# PIXRACER-POWER-R12.net
KiCad netlist of a schematic drawn in Altium Designer
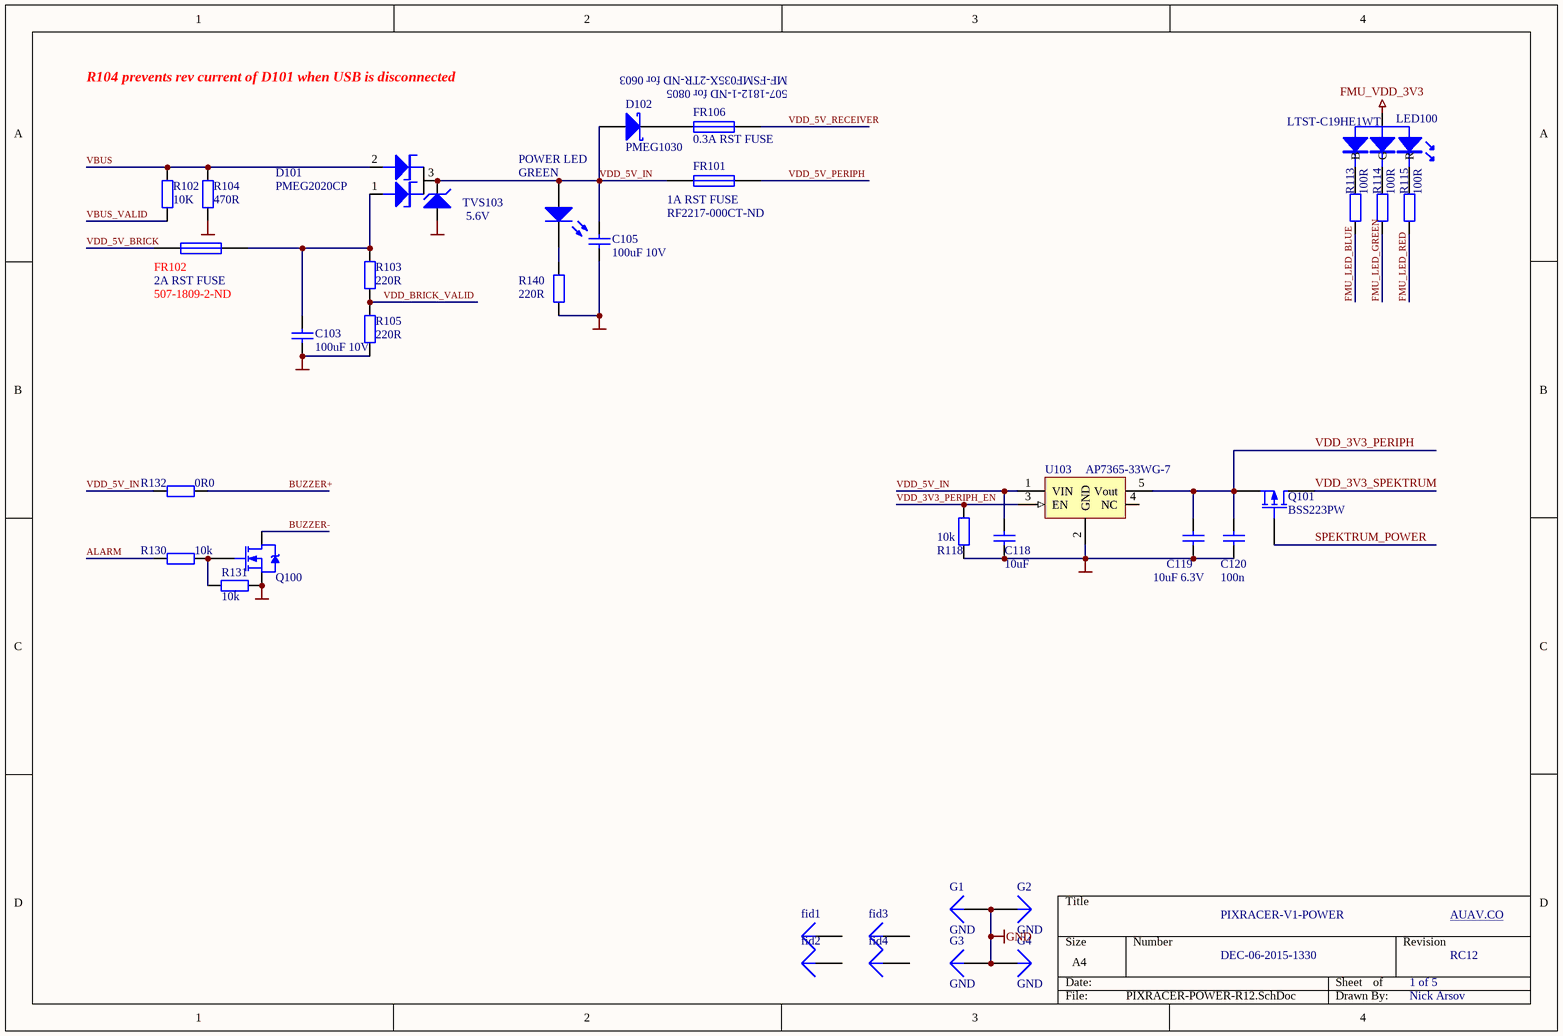
[diagram p0: PIXRACER-POWER-R12.SchDoc]

(export (version "E")
  (design (tool "Eeschema 10.0.6"))
  (components
    (comp (ref "C103")
      (value "100uF 10V")
      (footprint "0805A")
      (description "Capacitor")
      (fields (field (name "PUBLISHER") "Altium Limited"))
      (libsource (lib "Miscellaneous Devices") (part "Cap"))
    )
    (comp (ref "C105")
      (value "100uF 10V")
      (footprint "0805A")
      (description "Capacitor")
      (fields (field (name "PUBLISHER") "Altium Limited"))
      (libsource (lib "Miscellaneous Devices") (part "Cap"))
    )
    (comp (ref "C118")
      (value "10uF")
      (footprint "0603A")
      (description "Capacitor")
      (fields (field (name "PUBLISHER") "Altium Limited"))
      (libsource (lib "Miscellaneous Devices") (part "Cap"))
    )
    (comp (ref "C119")
      (value "10uF 6.3V")
      (footprint "0603A")
      (description "Capacitor")
      (fields (field (name "PUBLISHER") "Altium Limited"))
      (libsource (lib "Miscellaneous Devices") (part "Cap"))
    )
    (comp (ref "C120")
      (value "100n")
      (footprint "0603A")
      (description "Capacitor")
      (fields (field (name "PUBLISHER") "Altium Limited"))
      (libsource (lib "Miscellaneous Devices") (part "Cap"))
    )
    (comp (ref "D101")
      (value "PMEG2020CP")
      (footprint "pmeg2020cp")
      (libsource (lib "My_Altium") (part "PMEG2020CP"))
    )
    (comp (ref "D102")
      (value "PMEG1030")
      (footprint "sod323f")
      (description "Schottky Diode")
      (fields (field (name "PUBLISHER") "Altium Limited"))
      (libsource (lib "Miscellaneous Devices") (part "D Schottky"))
    )
    (comp (ref "fid1")
      (value "~")
      (footprint "SMT_PAD")
      (description "Plug")
      (fields (field (name "PUBLISHER") "Altium Limited"))
      (libsource (lib "Miscellaneous Connectors") (part "Plug"))
    )
    (comp (ref "fid2")
      (value "~")
      (footprint "SMT_PAD")
      (description "Plug")
      (fields (field (name "PUBLISHER") "Altium Limited"))
      (libsource (lib "Miscellaneous Connectors") (part "Plug"))
    )
    (comp (ref "fid3")
      (value "~")
      (footprint "SMT_PAD")
      (description "Plug")
      (fields (field (name "PUBLISHER") "Altium Limited"))
      (libsource (lib "Miscellaneous Connectors") (part "Plug"))
    )
    (comp (ref "fid4")
      (value "~")
      (footprint "SMT_PAD")
      (description "Plug")
      (fields (field (name "PUBLISHER") "Altium Limited"))
      (libsource (lib "Miscellaneous Connectors") (part "Plug"))
    )
    (comp (ref "FR101")
      (value "1A RST FUSE")
      (footprint "0805A")
      (description "Fuse")
      (fields (field (name "DIGIKEY") "RF2217-000CT-ND") (field (name "PUBLISHER") "Altium Limited"))
      (libsource (lib "Miscellaneous Devices") (part "Fuse 1"))
    )
    (comp (ref "FR102")
      (value "2A RST FUSE")
      (footprint "1206A")
      (description "Fuse")
      (fields (field (name "DIGIKEY") "507-1809-2-ND") (field (name "PUBLISHER") "Altium Limited"))
      (libsource (lib "Miscellaneous Devices") (part "Fuse 1"))
    )
    (comp (ref "FR106")
      (value "0.3A RST FUSE")
      (footprint "0805A")
      (description "Fuse")
      (fields (field (name "PUBLISHER") "Altium Limited"))
      (libsource (lib "Miscellaneous Devices") (part "Fuse 1"))
    )
    (comp (ref "G1")
      (value "GND")
      (description "Plug")
      (fields (field (name "PUBLISHER") "Altium Limited"))
      (libsource (lib "Miscellaneous Connectors") (part "Plug"))
    )
    (comp (ref "G2")
      (value "GND")
      (description "Plug")
      (fields (field (name "PUBLISHER") "Altium Limited"))
      (libsource (lib "Miscellaneous Connectors") (part "Plug"))
    )
    (comp (ref "G3")
      (value "GND")
      (description "Plug")
      (fields (field (name "PUBLISHER") "Altium Limited"))
      (libsource (lib "Miscellaneous Connectors") (part "Plug"))
    )
    (comp (ref "G4")
      (value "GND")
      (description "Plug")
      (fields (field (name "PUBLISHER") "Altium Limited"))
      (libsource (lib "Miscellaneous Connectors") (part "Plug"))
    )
    (comp (ref "LED100")
      (value "LTST-C19HE1WT")
      (footprint "LTST-C19HE1WT")
      (libsource (lib "My_Altium") (part "RGB_LED_5MM"))
    )
    (comp (ref "POWER LED")
      (value "GREEN")
      (footprint "0603A")
      (description "Typical INFRARED GaAs LED")
      (fields (field (name "PUBLISHER") "Altium Limited"))
      (libsource (lib "Miscellaneous Devices") (part "LED0"))
    )
    (comp (ref "Q100")
      (value "DMG1012UW")
      (footprint "2N7002-SOT323")
      (description "N-Channel Power MOSFET")
      (fields (field (name "PUBLISHER") "Altium Limited"))
      (libsource (lib "Miscellaneous Devices") (part "NMOS-2"))
    )
    (comp (ref "Q101")
      (value "BSS223PW")
      (footprint "2N7002-SOT323")
      (description "P-Channel MOSFET")
      (fields (field (name "PUBLISHER") "Altium Limited"))
      (libsource (lib "Miscellaneous Devices") (part "MOSFET-P"))
    )
    (comp (ref "R102")
      (value "10K")
      (footprint "0603A")
      (description "Resistor")
      (fields (field (name "PUBLISHER") "Altium Limited"))
      (libsource (lib "") (part "Res2_1"))
    )
    (comp (ref "R103")
      (value "220R")
      (footprint "0603A")
      (description "Resistor")
      (fields (field (name "PUBLISHER") "Altium Limited"))
      (libsource (lib "Miscellaneous Devices") (part "Res2"))
    )
    (comp (ref "R104")
      (value "470R")
      (footprint "0603A")
      (description "Resistor")
      (fields (field (name "PUBLISHER") "Altium Limited"))
      (libsource (lib "") (part "Res2_1"))
    )
    (comp (ref "R105")
      (value "220R")
      (footprint "0603A")
      (description "Resistor")
      (fields (field (name "PUBLISHER") "Altium Limited"))
      (libsource (lib "Miscellaneous Devices") (part "Res2"))
    )
    (comp (ref "R113")
      (value "100R")
      (footprint "0402A")
      (description "Resistor")
      (fields (field (name "PUBLISHER") "Altium Limited"))
      (libsource (lib "") (part "Res2_1"))
    )
    (comp (ref "R114")
      (value "100R")
      (footprint "0402A")
      (description "Resistor")
      (fields (field (name "PUBLISHER") "Altium Limited"))
      (libsource (lib "") (part "Res2_1"))
    )
    (comp (ref "R115")
      (value "100R")
      (footprint "0402A")
      (description "Resistor")
      (fields (field (name "PUBLISHER") "Altium Limited"))
      (libsource (lib "") (part "Res2_1"))
    )
    (comp (ref "R118")
      (value "10k")
      (footprint "0603A")
      (description "Resistor")
      (fields (field (name "PUBLISHER") "Altium Limited"))
      (libsource (lib "") (part "Res2_1"))
    )
    (comp (ref "R130")
      (value "10k")
      (footprint "0402A")
      (description "Resistor")
      (fields (field (name "PUBLISHER") "Altium Limited"))
      (libsource (lib "") (part "Res2_3"))
    )
    (comp (ref "R131")
      (value "10k")
      (footprint "0402A")
      (description "Resistor")
      (fields (field (name "PUBLISHER") "Altium Limited"))
      (libsource (lib "") (part "Res2_2"))
    )
    (comp (ref "R132")
      (value "0R0")
      (footprint "0402A")
      (description "Resistor")
      (fields (field (name "PUBLISHER") "Altium Limited"))
      (libsource (lib "") (part "Res2_3"))
    )
    (comp (ref "R140")
      (value "220R")
      (footprint "0603A")
      (description "Resistor")
      (fields (field (name "PUBLISHER") "Altium Limited"))
      (libsource (lib "") (part "Res2_1"))
    )
    (comp (ref "TVS103")
      (value "5.6V")
      (footprint "SOD123F")
      (description "Zener Diode")
      (fields (field (name "PUBLISHER") "Altium Limited"))
      (libsource (lib "Miscellaneous Devices") (part "D Zener"))
    )
    (comp (ref "U103")
      (value "AP7365-33WG-7")
      (footprint "SOT23-5")
      (libsource (lib "My_Altium") (part "LP5907-Q1"))
    )
  )
  (nets
    (net (code "1") (name "/ALARM") (class "Default")
      (node (ref "R130") (pin "2") (pinfunction "2_2") (pintype "passive"))
    )
    (net (code "2") (name "/BUZZER+") (class "Default")
      (node (ref "R132") (pin "1") (pinfunction "1_1") (pintype "passive"))
    )
    (net (code "3") (name "/BUZZER-") (class "Default")
      (node (ref "Q100") (pin "1") (pinfunction "D_1") (pintype "passive"))
    )
    (net (code "4") (name "/FMU_LED_BLUE") (class "Default")
      (node (ref "R113") (pin "1") (pinfunction "1_1") (pintype "passive"))
    )
    (net (code "5") (name "/FMU_LED_GREEN") (class "Default")
      (node (ref "R114") (pin "1") (pinfunction "1_1") (pintype "passive"))
    )
    (net (code "6") (name "/FMU_LED_RED") (class "Default")
      (node (ref "R115") (pin "1") (pinfunction "1_1") (pintype "passive"))
    )
    (net (code "7") (name "/SPEKTRUM_POWER") (class "Default")
      (node (ref "Q101") (pin "3") (pinfunction "G_3") (pintype "passive"))
    )
    (net (code "8") (name "/VBUS") (class "Default")
      (node (ref "D101") (pin "2") (pintype "passive"))
      (node (ref "R102") (pin "2") (pinfunction "2_2") (pintype "passive"))
      (node (ref "R104") (pin "2") (pinfunction "2_2") (pintype "passive"))
    )
    (net (code "9") (name "/VBUS_VALID") (class "Default")
      (node (ref "R102") (pin "1") (pinfunction "1_1") (pintype "passive"))
    )
    (net (code "10") (name "/VDD_3V3_PERIPH") (class "Default")
      (node (ref "C119") (pin "2") (pinfunction "2_2") (pintype "passive"))
      (node (ref "C120") (pin "2") (pinfunction "2_2") (pintype "passive"))
      (node (ref "Q101") (pin "2") (pinfunction "S_2") (pintype "passive"))
      (node (ref "U103") (pin "5") (pinfunction "Vout_5") (pintype "power_in"))
    )
    (net (code "11") (name "/VDD_3V3_PERIPH_EN") (class "Default")
      (node (ref "R118") (pin "2") (pinfunction "2_2") (pintype "passive"))
      (node (ref "U103") (pin "3") (pinfunction "EN_3") (pintype "input"))
    )
    (net (code "12") (name "/VDD_3V3_SPEKTRUM") (class "Default")
      (node (ref "Q101") (pin "1") (pinfunction "D_1") (pintype "passive"))
    )
    (net (code "13") (name "/VDD_5V_BRICK") (class "Default")
      (node (ref "FR102") (pin "1") (pinfunction "1_1") (pintype "passive"))
    )
    (net (code "14") (name "/VDD_5V_IN") (class "Default")
      (node (ref "C105") (pin "2") (pinfunction "2_2") (pintype "passive"))
      (node (ref "C118") (pin "2") (pinfunction "2_2") (pintype "passive"))
      (node (ref "D101") (pin "3") (pintype "passive"))
      (node (ref "D102") (pin "1") (pinfunction "A_1") (pintype "passive"))
      (node (ref "FR101") (pin "1") (pinfunction "1_1") (pintype "passive"))
      (node (ref "POWER LED") (pin "1") (pinfunction "A_1") (pintype "passive"))
      (node (ref "R132") (pin "2") (pinfunction "2_2") (pintype "passive"))
      (node (ref "TVS103") (pin "2") (pinfunction "K_2") (pintype "passive"))
      (node (ref "U103") (pin "1") (pinfunction "VIN_1") (pintype "power_in"))
    )
    (net (code "15") (name "/VDD_5V_PERIPH") (class "Default")
      (node (ref "FR101") (pin "2") (pinfunction "2_2") (pintype "passive"))
    )
    (net (code "16") (name "/VDD_5V_RECEIVER") (class "Default")
      (node (ref "FR106") (pin "2") (pinfunction "2_2") (pintype "passive"))
    )
    (net (code "17") (name "/VDD_BRICK_VALID") (class "Default")
      (node (ref "R103") (pin "2") (pinfunction "2_2") (pintype "passive"))
      (node (ref "R105") (pin "1") (pinfunction "1_1") (pintype "passive"))
    )
    (net (code "18") (name "FMU_VDD_3V3") (class "Default")
      (node (ref "LED100") (pin "4") (pinfunction "A_4") (pintype "passive"))
    )
    (net (code "19") (name "GND") (class "Default")
      (node (ref "C103") (pin "1") (pinfunction "1_1") (pintype "passive"))
      (node (ref "C105") (pin "1") (pinfunction "1_1") (pintype "passive"))
      (node (ref "C118") (pin "1") (pinfunction "1_1") (pintype "passive"))
      (node (ref "C119") (pin "1") (pinfunction "1_1") (pintype "passive"))
      (node (ref "C120") (pin "1") (pinfunction "1_1") (pintype "passive"))
      (node (ref "G1") (pin "1") (pinfunction "1_1") (pintype "passive"))
      (node (ref "G2") (pin "1") (pinfunction "1_1") (pintype "passive"))
      (node (ref "G3") (pin "1") (pinfunction "1_1") (pintype "passive"))
      (node (ref "G4") (pin "1") (pinfunction "1_1") (pintype "passive"))
      (node (ref "Q100") (pin "2") (pinfunction "S_2") (pintype "passive"))
      (node (ref "R104") (pin "1") (pinfunction "1_1") (pintype "passive"))
      (node (ref "R105") (pin "2") (pinfunction "2_2") (pintype "passive"))
      (node (ref "R118") (pin "1") (pinfunction "1_1") (pintype "passive"))
      (node (ref "R131") (pin "2") (pinfunction "2_2") (pintype "passive"))
      (node (ref "R140") (pin "1") (pinfunction "1_1") (pintype "passive"))
      (node (ref "TVS103") (pin "1") (pinfunction "A_1") (pintype "passive"))
      (node (ref "U103") (pin "2") (pinfunction "GND_2") (pintype "power_in"))
    )
    (net (code "20") (name "Net-(C103-Pad2)") (class "Default")
      (node (ref "C103") (pin "2") (pinfunction "2_2") (pintype "passive"))
      (node (ref "D101") (pin "1") (pintype "passive"))
      (node (ref "FR102") (pin "2") (pinfunction "2_2") (pintype "passive"))
      (node (ref "R103") (pin "1") (pinfunction "1_1") (pintype "passive"))
    )
    (net (code "21") (name "Net-(D102-K)") (class "Default")
      (node (ref "D102") (pin "2") (pinfunction "K_2") (pintype "passive"))
      (node (ref "FR106") (pin "1") (pinfunction "1_1") (pintype "passive"))
    )
    (net (code "22") (name "Net-(LED100-B)") (class "Default")
      (node (ref "LED100") (pin "3") (pinfunction "B_3") (pintype "passive"))
      (node (ref "R113") (pin "2") (pinfunction "2_2") (pintype "passive"))
    )
    (net (code "23") (name "Net-(LED100-G)") (class "Default")
      (node (ref "LED100") (pin "2") (pinfunction "G_2") (pintype "passive"))
      (node (ref "R114") (pin "2") (pinfunction "2_2") (pintype "passive"))
    )
    (net (code "24") (name "Net-(LED100-R)") (class "Default")
      (node (ref "LED100") (pin "1") (pinfunction "R_1") (pintype "passive"))
      (node (ref "R115") (pin "2") (pinfunction "2_2") (pintype "passive"))
    )
    (net (code "25") (name "Net-(POWER LED-K)") (class "Default")
      (node (ref "POWER LED") (pin "2") (pinfunction "K_2") (pintype "passive"))
      (node (ref "R140") (pin "2") (pinfunction "2_2") (pintype "passive"))
    )
    (net (code "26") (name "Net-(Q100-G)") (class "Default")
      (node (ref "Q100") (pin "3") (pinfunction "G_3") (pintype "passive"))
      (node (ref "R130") (pin "1") (pinfunction "1_1") (pintype "passive"))
      (node (ref "R131") (pin "1") (pinfunction "1_1") (pintype "passive"))
    )
    (net (code "27") (name "unconnected-(U103-NC-Pad4)") (class "Default")
      (node (ref "U103") (pin "4") (pinfunction "NC_4") (pintype "passive"))
    )
    (net (code "28") (name "unconnected-(fid1-Pad1)") (class "Default")
      (node (ref "fid1") (pin "1") (pinfunction "1_1") (pintype "passive"))
    )
    (net (code "29") (name "unconnected-(fid2-Pad1)") (class "Default")
      (node (ref "fid2") (pin "1") (pinfunction "1_1") (pintype "passive"))
    )
    (net (code "30") (name "unconnected-(fid3-Pad1)") (class "Default")
      (node (ref "fid3") (pin "1") (pinfunction "1_1") (pintype "passive"))
    )
    (net (code "31") (name "unconnected-(fid4-Pad1)") (class "Default")
      (node (ref "fid4") (pin "1") (pinfunction "1_1") (pintype "passive"))
    )
  )
)
